# relayChain5.net
KiCad netlist of a schematic drawn in EAGLE
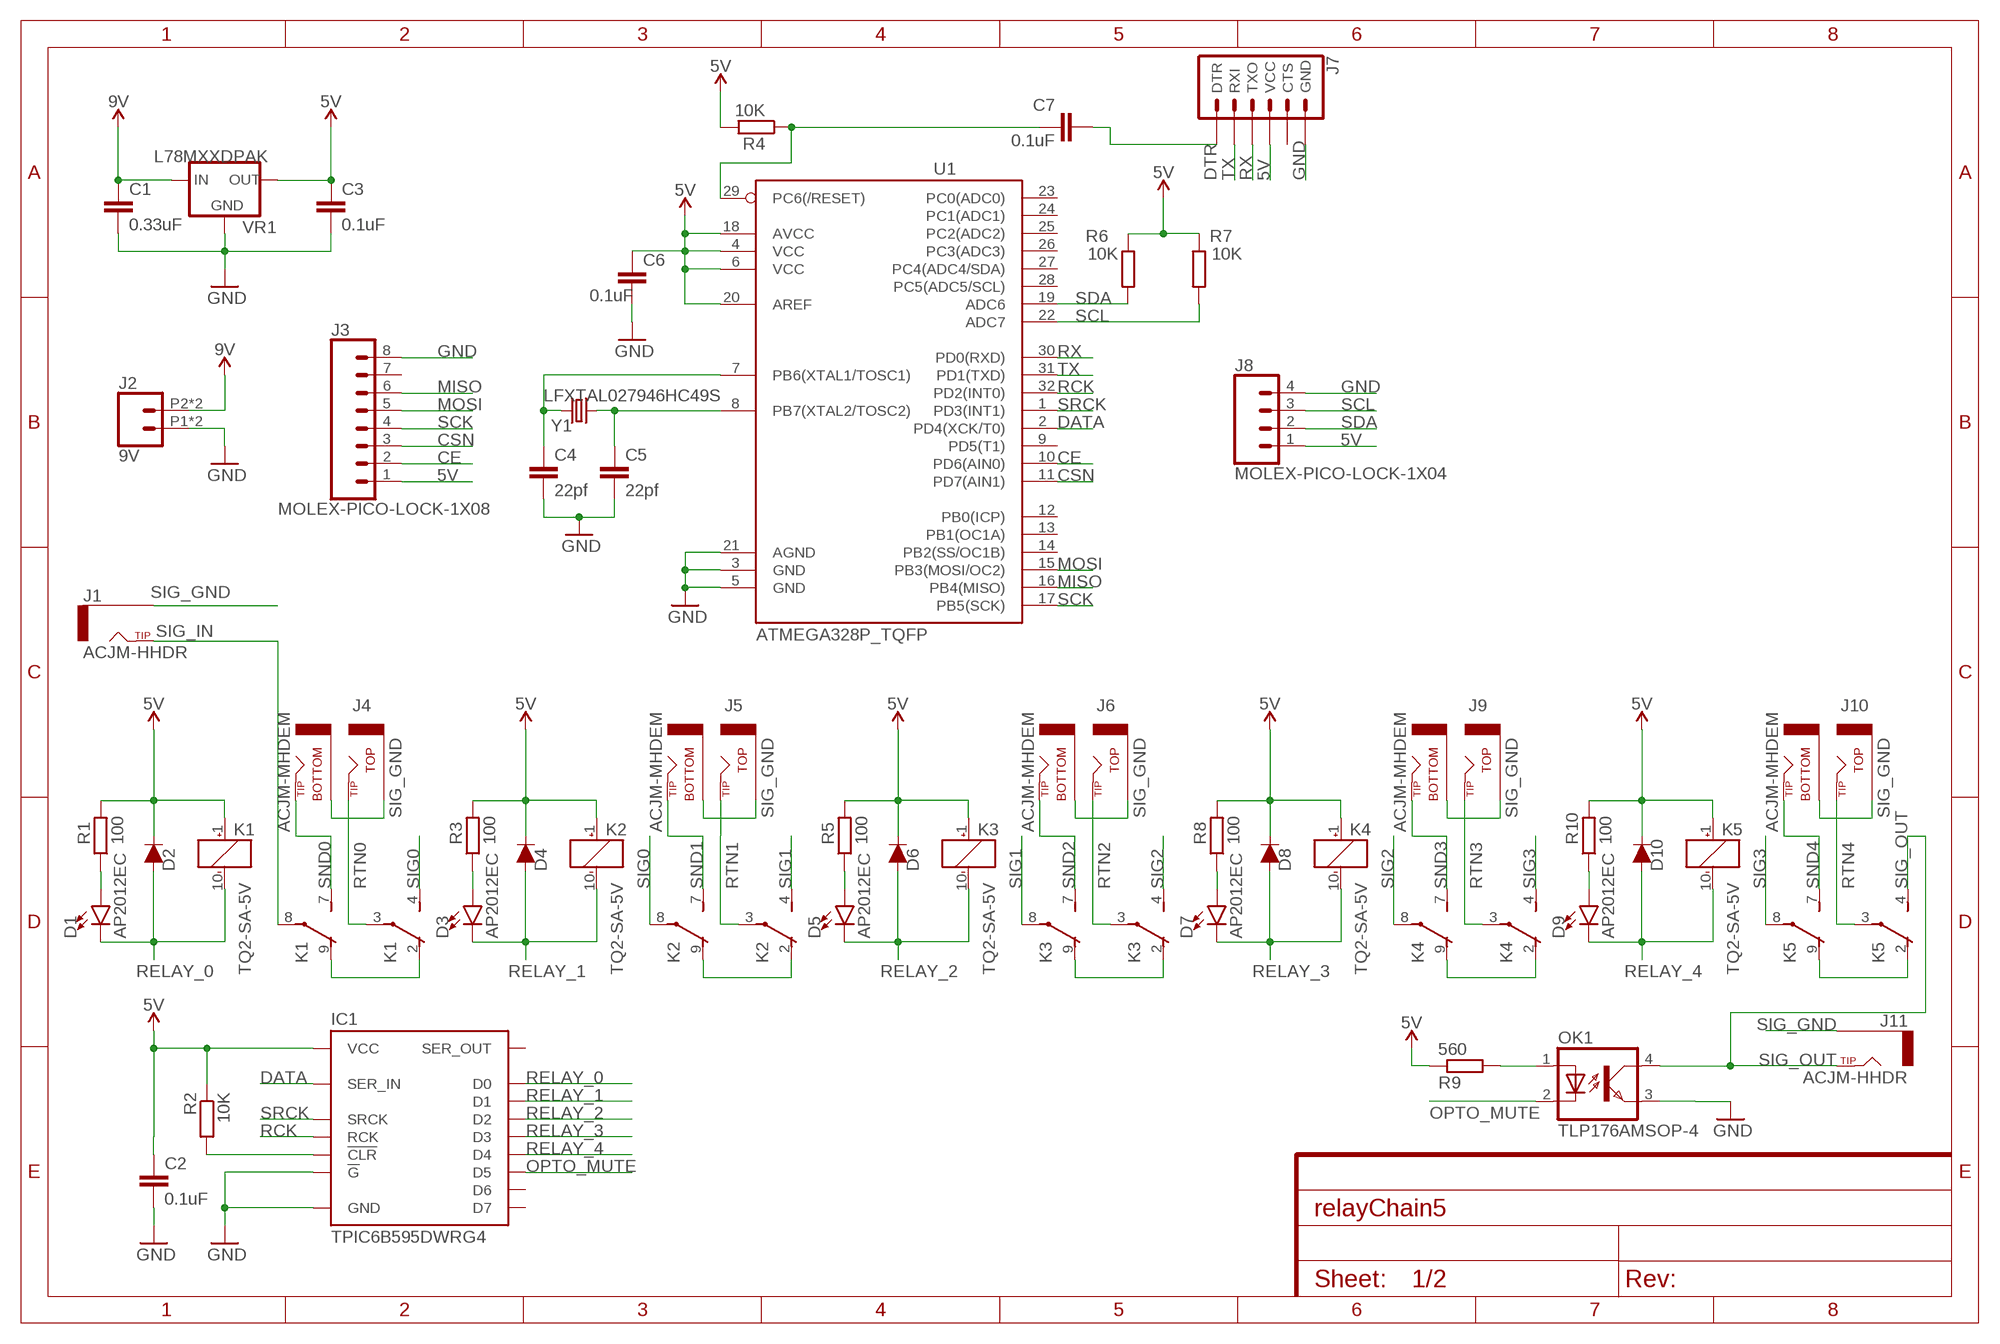
[diagram p0: schematic, sheet 1]
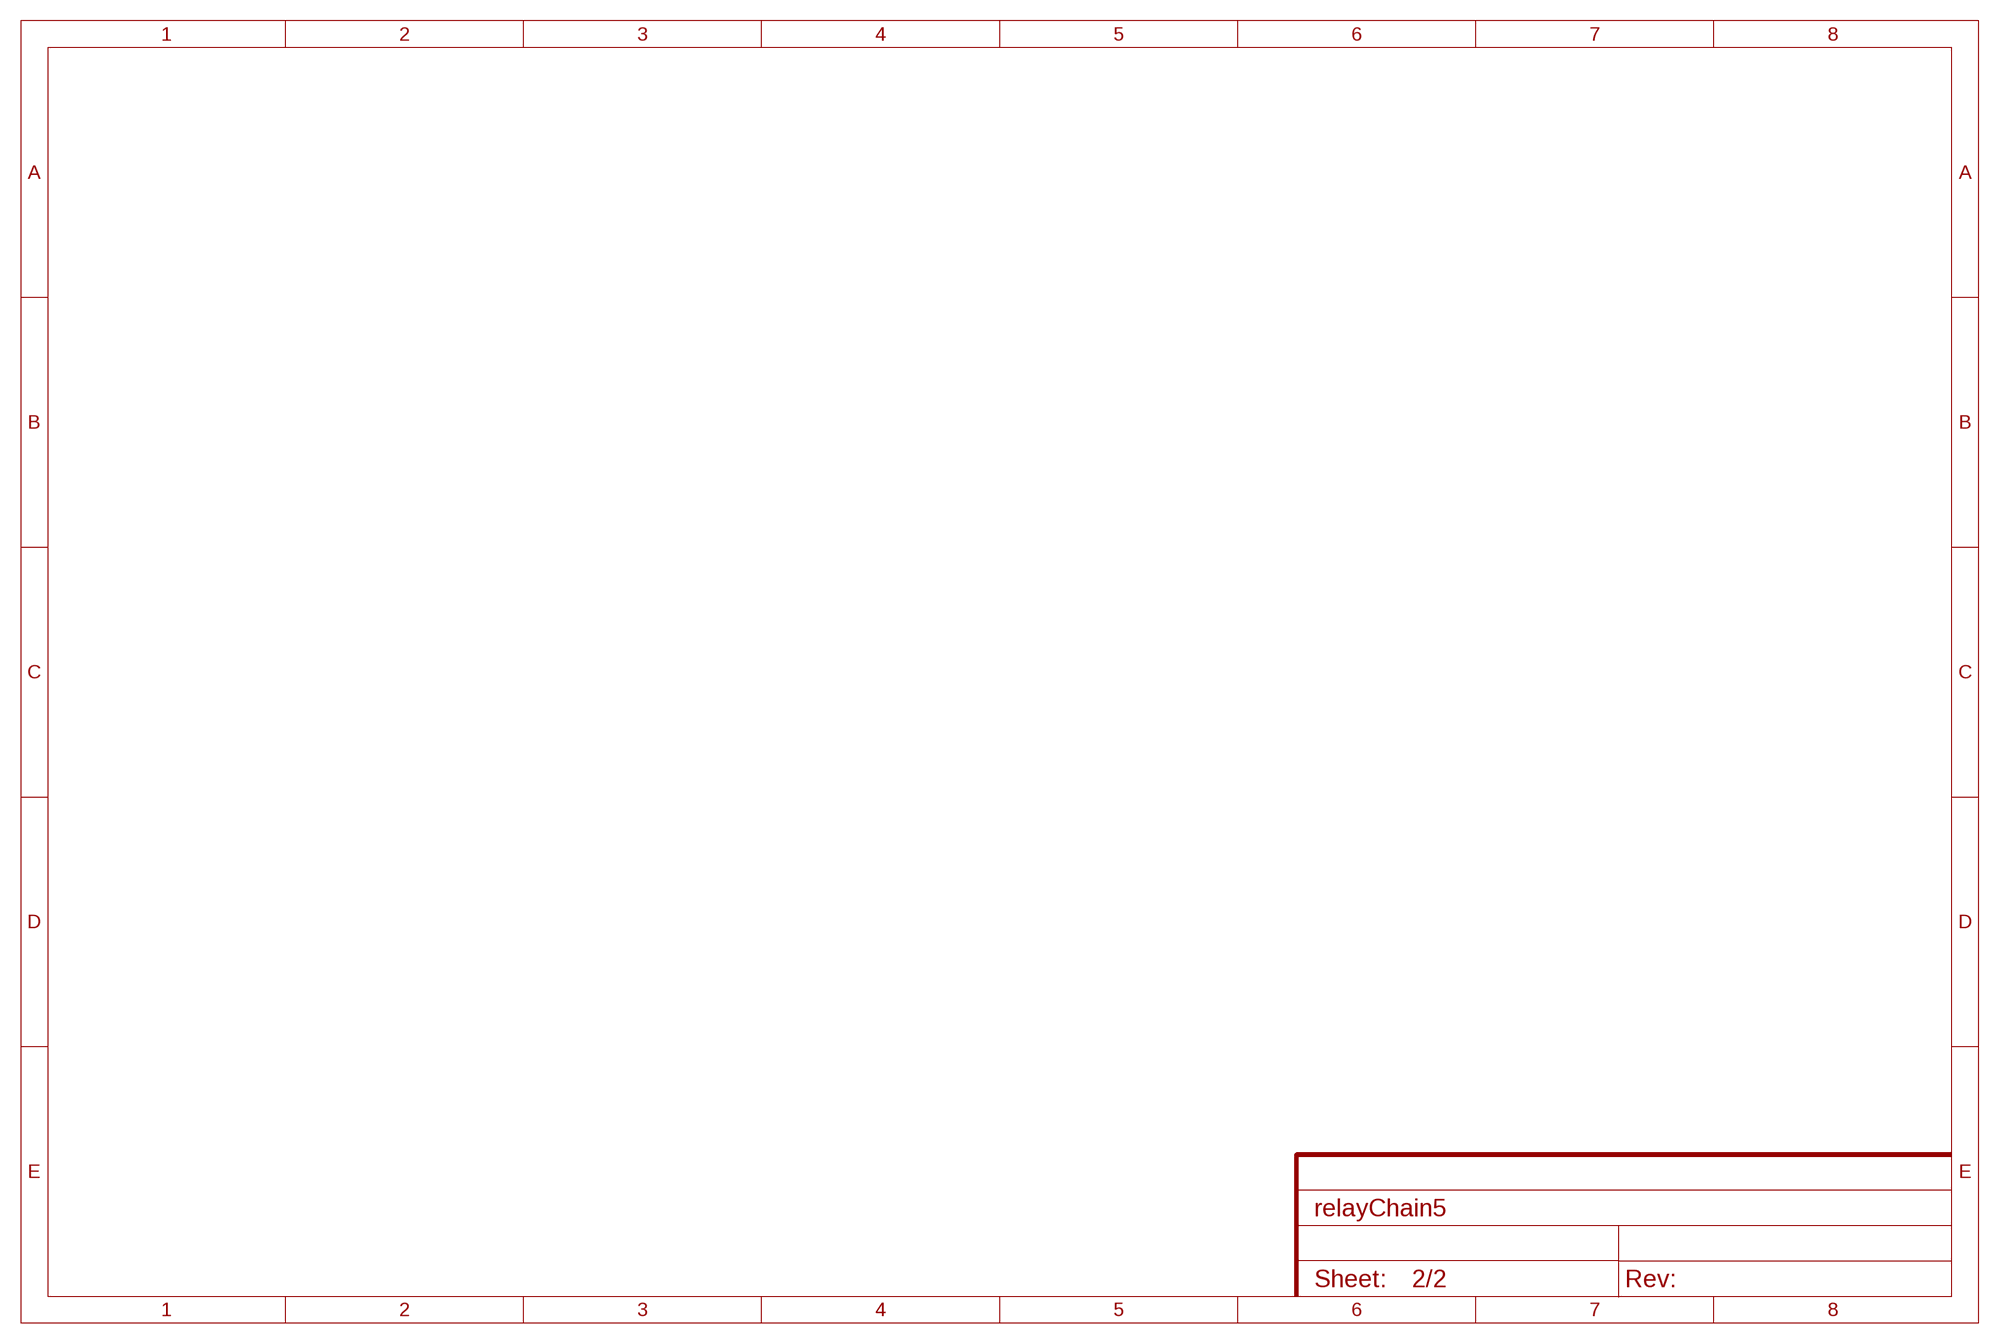
[diagram p1: schematic, sheet 2]

(export (version "E")
  (design (tool "Eeschema 10.0.6"))
  (components
    (comp (ref "C1")
      (value "0.33uF")
      (footprint "eagle-import:C0805")
      (libsource (lib "eagle-import") (part "C-EUC0805"))
    )
    (comp (ref "C2")
      (value "0.1uF")
      (footprint "eagle-import:C0805")
      (libsource (lib "eagle-import") (part "C-EUC0805"))
    )
    (comp (ref "C3")
      (value "0.1uF")
      (footprint "eagle-import:C0805")
      (libsource (lib "eagle-import") (part "C-EUC0805"))
    )
    (comp (ref "C4")
      (value "22pf")
      (footprint "eagle-import:C0805")
      (libsource (lib "eagle-import") (part "C-EUC0805"))
    )
    (comp (ref "C5")
      (value "22pf")
      (footprint "eagle-import:C0805")
      (libsource (lib "eagle-import") (part "C-EUC0805"))
    )
    (comp (ref "C6")
      (value "0.1uF")
      (footprint "eagle-import:C0805")
      (libsource (lib "eagle-import") (part "C-EUC0805"))
    )
    (comp (ref "C7")
      (value "0.1uF")
      (footprint "eagle-import:C0805")
      (libsource (lib "eagle-import") (part "C-EUC0805"))
    )
    (comp (ref "D1")
      (value "AP2012EC")
      (footprint "eagle-import:0805-LED-AP2012EC")
      (libsource (lib "eagle-import") (part "AP2012EC"))
    )
    (comp (ref "D2")
      (value "1n4148")
      (footprint "eagle-import:SOD-123_MINI-SMA")
      (libsource (lib "eagle-import") (part "621-1N4148?"))
    )
    (comp (ref "D3")
      (value "AP2012EC")
      (footprint "eagle-import:0805-LED-AP2012EC")
      (libsource (lib "eagle-import") (part "AP2012EC"))
    )
    (comp (ref "D4")
      (value "1n4148")
      (footprint "eagle-import:SOD-123_MINI-SMA")
      (libsource (lib "eagle-import") (part "621-1N4148?"))
    )
    (comp (ref "D5")
      (value "AP2012EC")
      (footprint "eagle-import:0805-LED-AP2012EC")
      (libsource (lib "eagle-import") (part "AP2012EC"))
    )
    (comp (ref "D6")
      (value "1n4148")
      (footprint "eagle-import:SOD-123_MINI-SMA")
      (libsource (lib "eagle-import") (part "621-1N4148?"))
    )
    (comp (ref "D7")
      (value "AP2012EC")
      (footprint "eagle-import:0805-LED-AP2012EC")
      (libsource (lib "eagle-import") (part "AP2012EC"))
    )
    (comp (ref "D8")
      (value "1n4148")
      (footprint "eagle-import:SOD-123_MINI-SMA")
      (libsource (lib "eagle-import") (part "621-1N4148?"))
    )
    (comp (ref "D9")
      (value "AP2012EC")
      (footprint "eagle-import:0805-LED-AP2012EC")
      (libsource (lib "eagle-import") (part "AP2012EC"))
    )
    (comp (ref "D10")
      (value "1n4148")
      (footprint "eagle-import:SOD-123_MINI-SMA")
      (libsource (lib "eagle-import") (part "621-1N4148?"))
    )
    (comp (ref "IC1")
      (value "TPIC6B595DWRG4")
      (footprint "eagle-import:SOIC127P1032X265-20")
      (libsource (lib "eagle-import") (part "TPIC6B595DWRG4"))
    )
    (comp (ref "J1")
      (value "ACJM-HHDR")
      (footprint "eagle-import:ACJM-HHDR")
      (libsource (lib "eagle-import") (part "ACJM-HHDR"))
    )
    (comp (ref "J2")
      (value "9V")
      (footprint "eagle-import:1X02_POKEHOME")
      (libsource (lib "eagle-import") (part "CONN_02SMALL_POKEHOME"))
    )
    (comp (ref "J3")
      (value "MOLEX-PICO-LOCK-1X08")
      (footprint "eagle-import:MOLEX-PICO-LOCK-1X08")
      (libsource (lib "eagle-import") (part "MOLEX-PICO-LOCK-1X08"))
    )
    (comp (ref "J4")
      (value "ACJM-MHDEM")
      (footprint "eagle-import:ACJM-MHDEM")
      (libsource (lib "eagle-import") (part "ACJM-MHDEM"))
    )
    (comp (ref "J5")
      (value "ACJM-MHDEM")
      (footprint "eagle-import:ACJM-MHDEM")
      (libsource (lib "eagle-import") (part "ACJM-MHDEM"))
    )
    (comp (ref "J6")
      (value "ACJM-MHDEM")
      (footprint "eagle-import:ACJM-MHDEM")
      (libsource (lib "eagle-import") (part "ACJM-MHDEM"))
    )
    (comp (ref "J7")
      (value "6_PIN_SERIAL_TARGETPTH-KIT")
      (footprint "eagle-import:1X06-KIT")
      (libsource (lib "eagle-import") (part "6_PIN_SERIAL_TARGETPTH-KIT"))
    )
    (comp (ref "J8")
      (value "MOLEX-PICO-LOCK-1X04")
      (footprint "eagle-import:MOLEX-PICO-LOCK-1X04")
      (libsource (lib "eagle-import") (part "MOLEX-PICO-LOCK-1X04"))
    )
    (comp (ref "J9")
      (value "ACJM-MHDEM")
      (footprint "eagle-import:ACJM-MHDEM")
      (libsource (lib "eagle-import") (part "ACJM-MHDEM"))
    )
    (comp (ref "J10")
      (value "ACJM-MHDEM")
      (footprint "eagle-import:ACJM-MHDEM")
      (libsource (lib "eagle-import") (part "ACJM-MHDEM"))
    )
    (comp (ref "J11")
      (value "ACJM-HHDR")
      (footprint "eagle-import:ACJM-HHDR")
      (libsource (lib "eagle-import") (part "ACJM-HHDR"))
    )
    (comp (ref "K1")
      (value "TQ2-SA-5V")
      (footprint "eagle-import:TQ-SA")
      (fields (field (name "MF") "AROMAT/ MATSUSHITA") (field (name "MPN") "TQ2SA-5V"))
      (libsource (lib "eagle-import") (part "TQ2?-SA-5V"))
    )
    (comp (ref "K2")
      (value "TQ2-SA-5V")
      (footprint "eagle-import:TQ-SA")
      (fields (field (name "MF") "AROMAT/ MATSUSHITA") (field (name "MPN") "TQ2SA-5V"))
      (libsource (lib "eagle-import") (part "TQ2?-SA-5V"))
    )
    (comp (ref "K3")
      (value "TQ2-SA-5V")
      (footprint "eagle-import:TQ-SA")
      (fields (field (name "MF") "AROMAT/ MATSUSHITA") (field (name "MPN") "TQ2SA-5V"))
      (libsource (lib "eagle-import") (part "TQ2?-SA-5V"))
    )
    (comp (ref "K4")
      (value "TQ2-SA-5V")
      (footprint "eagle-import:TQ-SA")
      (fields (field (name "MF") "AROMAT/ MATSUSHITA") (field (name "MPN") "TQ2SA-5V"))
      (libsource (lib "eagle-import") (part "TQ2?-SA-5V"))
    )
    (comp (ref "K5")
      (value "TQ2-SA-5V")
      (footprint "eagle-import:TQ-SA")
      (fields (field (name "MF") "AROMAT/ MATSUSHITA") (field (name "MPN") "TQ2SA-5V"))
      (libsource (lib "eagle-import") (part "TQ2?-SA-5V"))
    )
    (comp (ref "OK1")
      (value "TLP176AMSOP-4")
      (footprint "eagle-import:SOP254P715X220-4")
      (libsource (lib "eagle-import") (part "TLP176AMSOP-4"))
    )
    (comp (ref "R1")
      (value "100")
      (footprint "eagle-import:M2012")
      (libsource (lib "eagle-import") (part "R-EU_M2012"))
    )
    (comp (ref "R2")
      (value "10K")
      (footprint "eagle-import:R0805")
      (libsource (lib "eagle-import") (part "R-EU_R0805"))
    )
    (comp (ref "R3")
      (value "100")
      (footprint "eagle-import:M2012")
      (libsource (lib "eagle-import") (part "R-EU_M2012"))
    )
    (comp (ref "R4")
      (value "10K")
      (footprint "eagle-import:M2012")
      (libsource (lib "eagle-import") (part "R-EU_M2012"))
    )
    (comp (ref "R5")
      (value "100")
      (footprint "eagle-import:M2012")
      (libsource (lib "eagle-import") (part "R-EU_M2012"))
    )
    (comp (ref "R6")
      (value "10K")
      (footprint "eagle-import:M2012")
      (libsource (lib "eagle-import") (part "R-EU_M2012"))
    )
    (comp (ref "R7")
      (value "10K")
      (footprint "eagle-import:M2012")
      (libsource (lib "eagle-import") (part "R-EU_M2012"))
    )
    (comp (ref "R8")
      (value "100")
      (footprint "eagle-import:M2012")
      (libsource (lib "eagle-import") (part "R-EU_M2012"))
    )
    (comp (ref "R9")
      (value "560")
      (footprint "eagle-import:R0805")
      (libsource (lib "eagle-import") (part "R-EU_R0805"))
    )
    (comp (ref "R10")
      (value "100")
      (footprint "eagle-import:M2012")
      (libsource (lib "eagle-import") (part "R-EU_M2012"))
    )
    (comp (ref "U1")
      (value "ATMEGA328P_TQFP")
      (footprint "eagle-import:TQFP32-08")
      (libsource (lib "eagle-import") (part "ATMEGA328P_TQFP"))
    )
    (comp (ref "VR1")
      (value "L78MXXDPAK")
      (footprint "eagle-import:TO457P972X240-3")
      (libsource (lib "eagle-import") (part "L78MXX?DPAK"))
    )
    (comp (ref "Y1")
      (value "LFXTAL027946HC49S")
      (footprint "eagle-import:XTAL1150X490X450")
      (libsource (lib "eagle-import") (part "LFXTAL027946HC49S"))
    )
  )
  (nets
    (net (code "1") (name "5V") (class "Default")
      (node (ref "C2") (pin "1") (pinfunction "1_1") (pintype "passive"))
      (node (ref "C3") (pin "1") (pinfunction "1_1") (pintype "passive"))
      (node (ref "C6") (pin "1") (pinfunction "1_1") (pintype "passive"))
      (node (ref "D10") (pin "C") (pinfunction "C_C") (pintype "passive"))
      (node (ref "D2") (pin "C") (pinfunction "C_C") (pintype "passive"))
      (node (ref "D4") (pin "C") (pinfunction "C_C") (pintype "passive"))
      (node (ref "D6") (pin "C") (pinfunction "C_C") (pintype "passive"))
      (node (ref "D8") (pin "C") (pinfunction "C_C") (pintype "passive"))
      (node (ref "IC1") (pin "2") (pinfunction "VCC_2") (pintype "power_in"))
      (node (ref "J3") (pin "1") (pinfunction "1_1") (pintype "passive"))
      (node (ref "J7") (pin "4") (pinfunction "VCC_4") (pintype "passive"))
      (node (ref "J8") (pin "1") (pinfunction "1_1") (pintype "passive"))
      (node (ref "K1") (pin "1") (pinfunction "+_1") (pintype "passive"))
      (node (ref "K2") (pin "1") (pinfunction "+_1") (pintype "passive"))
      (node (ref "K3") (pin "1") (pinfunction "+_1") (pintype "passive"))
      (node (ref "K4") (pin "1") (pinfunction "+_1") (pintype "passive"))
      (node (ref "K5") (pin "1") (pinfunction "+_1") (pintype "passive"))
      (node (ref "R1") (pin "2") (pinfunction "2_2") (pintype "passive"))
      (node (ref "R10") (pin "2") (pinfunction "2_2") (pintype "passive"))
      (node (ref "R2") (pin "1") (pinfunction "1_1") (pintype "passive"))
      (node (ref "R3") (pin "2") (pinfunction "2_2") (pintype "passive"))
      (node (ref "R4") (pin "2") (pinfunction "2_2") (pintype "passive"))
      (node (ref "R5") (pin "2") (pinfunction "2_2") (pintype "passive"))
      (node (ref "R6") (pin "1") (pinfunction "1_1") (pintype "passive"))
      (node (ref "R7") (pin "1") (pinfunction "1_1") (pintype "passive"))
      (node (ref "R8") (pin "2") (pinfunction "2_2") (pintype "passive"))
      (node (ref "R9") (pin "1") (pinfunction "1_1") (pintype "passive"))
      (node (ref "U1") (pin "18") (pinfunction "AVCC_18") (pintype "bidirectional"))
      (node (ref "U1") (pin "20") (pinfunction "AREF_20") (pintype "bidirectional"))
      (node (ref "U1") (pin "4") (pinfunction "VCC_4") (pintype "bidirectional"))
      (node (ref "U1") (pin "6") (pinfunction "VCC_6") (pintype "bidirectional"))
      (node (ref "VR1") (pin "2") (pinfunction "OUT_2") (pintype "passive"))
    )
    (net (code "2") (name "9V") (class "Default")
      (node (ref "C1") (pin "1") (pinfunction "1_1") (pintype "passive"))
      (node (ref "J2") (pin "P2") (pinfunction "2_P2") (pintype "passive"))
      (node (ref "J2") (pin "P4") (pinfunction "2_P4") (pintype "passive"))
      (node (ref "VR1") (pin "1") (pinfunction "IN_1") (pintype "input"))
    )
    (net (code "3") (name "CE") (class "Default")
      (node (ref "J3") (pin "2") (pinfunction "2_2") (pintype "passive"))
      (node (ref "U1") (pin "10") (pinfunction "PD6(AIN0)_10") (pintype "bidirectional"))
    )
    (net (code "4") (name "CSN") (class "Default")
      (node (ref "J3") (pin "3") (pinfunction "3_3") (pintype "passive"))
      (node (ref "U1") (pin "11") (pinfunction "PD7(AIN1)_11") (pintype "bidirectional"))
    )
    (net (code "5") (name "DATA") (class "Default")
      (node (ref "IC1") (pin "3") (pinfunction "SER_IN_3") (pintype "input"))
      (node (ref "U1") (pin "2") (pinfunction "PD4(XCK/T0)_2") (pintype "bidirectional"))
    )
    (net (code "6") (name "DTR") (class "Default")
      (node (ref "C7") (pin "2") (pinfunction "2_2") (pintype "passive"))
      (node (ref "J7") (pin "1") (pinfunction "DTR_1") (pintype "passive"))
    )
    (net (code "7") (name "GND") (class "Default")
      (node (ref "C1") (pin "2") (pinfunction "2_2") (pintype "passive"))
      (node (ref "C2") (pin "2") (pinfunction "2_2") (pintype "passive"))
      (node (ref "C3") (pin "2") (pinfunction "2_2") (pintype "passive"))
      (node (ref "C4") (pin "2") (pinfunction "2_2") (pintype "passive"))
      (node (ref "C5") (pin "2") (pinfunction "2_2") (pintype "passive"))
      (node (ref "C6") (pin "2") (pinfunction "2_2") (pintype "passive"))
      (node (ref "IC1") (pin "10") (pinfunction "GND_10") (pintype "power_in"))
      (node (ref "IC1") (pin "11") (pinfunction "GND_11") (pintype "power_in"))
      (node (ref "IC1") (pin "19") (pinfunction "GND_19") (pintype "power_in"))
      (node (ref "IC1") (pin "9") (pinfunction "~{G}_9") (pintype "input"))
      (node (ref "J2") (pin "P1") (pinfunction "1_P1") (pintype "passive"))
      (node (ref "J2") (pin "P3") (pinfunction "1_P3") (pintype "passive"))
      (node (ref "J3") (pin "8") (pinfunction "8_8") (pintype "passive"))
      (node (ref "J7") (pin "6") (pinfunction "GND_6") (pintype "passive"))
      (node (ref "J8") (pin "4") (pinfunction "4_4") (pintype "passive"))
      (node (ref "OK1") (pin "3") (pinfunction "EMIT_3") (pintype "passive"))
      (node (ref "U1") (pin "21") (pinfunction "AGND_21") (pintype "bidirectional"))
      (node (ref "U1") (pin "3") (pinfunction "GND_3") (pintype "bidirectional"))
      (node (ref "U1") (pin "5") (pinfunction "GND_5") (pintype "bidirectional"))
      (node (ref "VR1") (pin "3") (pinfunction "GND_3") (pintype "input"))
    )
    (net (code "8") (name "MISO") (class "Default")
      (node (ref "J3") (pin "6") (pinfunction "6_6") (pintype "passive"))
      (node (ref "U1") (pin "16") (pinfunction "PB4(MISO)_16") (pintype "bidirectional"))
    )
    (net (code "9") (name "MOSI") (class "Default")
      (node (ref "J3") (pin "5") (pinfunction "5_5") (pintype "passive"))
      (node (ref "U1") (pin "15") (pinfunction "PB3(MOSI/OC2)_15") (pintype "bidirectional"))
    )
    (net (code "10") (name "Net-(D1-PadA)") (class "Default")
      (node (ref "D1") (pin "A") (pinfunction "A_A") (pintype "passive"))
      (node (ref "R1") (pin "1") (pinfunction "1_1") (pintype "passive"))
    )
    (net (code "11") (name "Net-(D3-PadA)") (class "Default")
      (node (ref "D3") (pin "A") (pinfunction "A_A") (pintype "passive"))
      (node (ref "R3") (pin "1") (pinfunction "1_1") (pintype "passive"))
    )
    (net (code "12") (name "Net-(D5-PadA)") (class "Default")
      (node (ref "D5") (pin "A") (pinfunction "A_A") (pintype "passive"))
      (node (ref "R5") (pin "1") (pinfunction "1_1") (pintype "passive"))
    )
    (net (code "13") (name "Net-(D7-PadA)") (class "Default")
      (node (ref "D7") (pin "A") (pinfunction "A_A") (pintype "passive"))
      (node (ref "R8") (pin "1") (pinfunction "1_1") (pintype "passive"))
    )
    (net (code "14") (name "Net-(D9-PadA)") (class "Default")
      (node (ref "D9") (pin "A") (pinfunction "A_A") (pintype "passive"))
      (node (ref "R10") (pin "1") (pinfunction "1_1") (pintype "passive"))
    )
    (net (code "15") (name "Net-(IC1-~{CLR})") (class "Default")
      (node (ref "IC1") (pin "8") (pinfunction "~{CLR}_8") (pintype "input"))
      (node (ref "R2") (pin "2") (pinfunction "2_2") (pintype "passive"))
    )
    (net (code "16") (name "Net-(K1A-O)") (class "Default")
      (node (ref "K1") (pin "2") (pinfunction "O_2") (pintype "passive"))
      (node (ref "K1") (pin "9") (pinfunction "O_9") (pintype "passive"))
    )
    (net (code "17") (name "Net-(K2A-O)") (class "Default")
      (node (ref "K2") (pin "2") (pinfunction "O_2") (pintype "passive"))
      (node (ref "K2") (pin "9") (pinfunction "O_9") (pintype "passive"))
    )
    (net (code "18") (name "Net-(K3A-O)") (class "Default")
      (node (ref "K3") (pin "2") (pinfunction "O_2") (pintype "passive"))
      (node (ref "K3") (pin "9") (pinfunction "O_9") (pintype "passive"))
    )
    (net (code "19") (name "Net-(K4A-O)") (class "Default")
      (node (ref "K4") (pin "2") (pinfunction "O_2") (pintype "passive"))
      (node (ref "K4") (pin "9") (pinfunction "O_9") (pintype "passive"))
    )
    (net (code "20") (name "Net-(K5A-O)") (class "Default")
      (node (ref "K5") (pin "2") (pinfunction "O_2") (pintype "passive"))
      (node (ref "K5") (pin "9") (pinfunction "O_9") (pintype "passive"))
    )
    (net (code "21") (name "Net-(OK1-A)") (class "Default")
      (node (ref "OK1") (pin "1") (pinfunction "A_1") (pintype "passive"))
      (node (ref "R9") (pin "2") (pinfunction "2_2") (pintype "passive"))
    )
    (net (code "22") (name "Net-(U1-PB6(XTAL1{slash}TOSC1))") (class "Default")
      (node (ref "C4") (pin "1") (pinfunction "1_1") (pintype "passive"))
      (node (ref "U1") (pin "7") (pinfunction "PB6(XTAL1/TOSC1)_7") (pintype "bidirectional"))
      (node (ref "Y1") (pin "1") (pinfunction "1_1") (pintype "passive"))
    )
    (net (code "23") (name "Net-(U1-PB7(XTAL2{slash}TOSC2))") (class "Default")
      (node (ref "C5") (pin "1") (pinfunction "1_1") (pintype "passive"))
      (node (ref "U1") (pin "8") (pinfunction "PB7(XTAL2/TOSC2)_8") (pintype "bidirectional"))
      (node (ref "Y1") (pin "2") (pinfunction "2_2") (pintype "passive"))
    )
    (net (code "24") (name "Net-(U1-PC6({slash}RESET))") (class "Default")
      (node (ref "C7") (pin "1") (pinfunction "1_1") (pintype "passive"))
      (node (ref "R4") (pin "1") (pinfunction "1_1") (pintype "passive"))
      (node (ref "U1") (pin "29") (pinfunction "PC6(/RESET)_29") (pintype "bidirectional"))
    )
    (net (code "25") (name "OPTO_MUTE") (class "Default")
      (node (ref "IC1") (pin "15") (pinfunction "D5_15") (pintype "output"))
      (node (ref "OK1") (pin "2") (pinfunction "C_2") (pintype "passive"))
    )
    (net (code "26") (name "RCK") (class "Default")
      (node (ref "IC1") (pin "12") (pinfunction "RCK_12") (pintype "input"))
      (node (ref "U1") (pin "32") (pinfunction "PD2(INT0)_32") (pintype "bidirectional"))
    )
    (net (code "27") (name "RELAY_0") (class "Default")
      (node (ref "D1") (pin "C") (pinfunction "C_C") (pintype "passive"))
      (node (ref "D2") (pin "A") (pinfunction "A_A") (pintype "passive"))
      (node (ref "IC1") (pin "4") (pinfunction "D0_4") (pintype "output"))
      (node (ref "K1") (pin "10") (pinfunction "-_10") (pintype "passive"))
    )
    (net (code "28") (name "RELAY_1") (class "Default")
      (node (ref "D3") (pin "C") (pinfunction "C_C") (pintype "passive"))
      (node (ref "D4") (pin "A") (pinfunction "A_A") (pintype "passive"))
      (node (ref "IC1") (pin "5") (pinfunction "D1_5") (pintype "output"))
      (node (ref "K2") (pin "10") (pinfunction "-_10") (pintype "passive"))
    )
    (net (code "29") (name "RELAY_2") (class "Default")
      (node (ref "D5") (pin "C") (pinfunction "C_C") (pintype "passive"))
      (node (ref "D6") (pin "A") (pinfunction "A_A") (pintype "passive"))
      (node (ref "IC1") (pin "6") (pinfunction "D2_6") (pintype "output"))
      (node (ref "K3") (pin "10") (pinfunction "-_10") (pintype "passive"))
    )
    (net (code "30") (name "RELAY_3") (class "Default")
      (node (ref "D7") (pin "C") (pinfunction "C_C") (pintype "passive"))
      (node (ref "D8") (pin "A") (pinfunction "A_A") (pintype "passive"))
      (node (ref "IC1") (pin "7") (pinfunction "D3_7") (pintype "output"))
      (node (ref "K4") (pin "10") (pinfunction "-_10") (pintype "passive"))
    )
    (net (code "31") (name "RELAY_4") (class "Default")
      (node (ref "D10") (pin "A") (pinfunction "A_A") (pintype "passive"))
      (node (ref "D9") (pin "C") (pinfunction "C_C") (pintype "passive"))
      (node (ref "IC1") (pin "14") (pinfunction "D4_14") (pintype "output"))
      (node (ref "K5") (pin "10") (pinfunction "-_10") (pintype "passive"))
    )
    (net (code "32") (name "RTN0") (class "Default")
      (node (ref "J4") (pin "12") (pinfunction "TIP_TOP_12") (pintype "bidirectional"))
      (node (ref "J4") (pin "9") (pinfunction "TIP_TOP_9") (pintype "bidirectional"))
      (node (ref "K1") (pin "3") (pinfunction "P_3") (pintype "passive"))
    )
    (net (code "33") (name "RTN1") (class "Default")
      (node (ref "J5") (pin "12") (pinfunction "TIP_TOP_12") (pintype "bidirectional"))
      (node (ref "J5") (pin "9") (pinfunction "TIP_TOP_9") (pintype "bidirectional"))
      (node (ref "K2") (pin "3") (pinfunction "P_3") (pintype "passive"))
    )
    (net (code "34") (name "RTN2") (class "Default")
      (node (ref "J6") (pin "12") (pinfunction "TIP_TOP_12") (pintype "bidirectional"))
      (node (ref "J6") (pin "9") (pinfunction "TIP_TOP_9") (pintype "bidirectional"))
      (node (ref "K3") (pin "3") (pinfunction "P_3") (pintype "passive"))
    )
    (net (code "35") (name "RTN3") (class "Default")
      (node (ref "J9") (pin "12") (pinfunction "TIP_TOP_12") (pintype "bidirectional"))
      (node (ref "J9") (pin "9") (pinfunction "TIP_TOP_9") (pintype "bidirectional"))
      (node (ref "K4") (pin "3") (pinfunction "P_3") (pintype "passive"))
    )
    (net (code "36") (name "RTN4") (class "Default")
      (node (ref "J10") (pin "12") (pinfunction "TIP_TOP_12") (pintype "bidirectional"))
      (node (ref "J10") (pin "9") (pinfunction "TIP_TOP_9") (pintype "bidirectional"))
      (node (ref "K5") (pin "3") (pinfunction "P_3") (pintype "passive"))
    )
    (net (code "37") (name "RX") (class "Default")
      (node (ref "J7") (pin "3") (pinfunction "TXO_3") (pintype "passive"))
      (node (ref "U1") (pin "30") (pinfunction "PD0(RXD)_30") (pintype "bidirectional"))
    )
    (net (code "38") (name "SCK") (class "Default")
      (node (ref "J3") (pin "4") (pinfunction "4_4") (pintype "passive"))
      (node (ref "U1") (pin "17") (pinfunction "PB5(SCK)_17") (pintype "bidirectional"))
    )
    (net (code "39") (name "SCL") (class "Default")
      (node (ref "J8") (pin "3") (pinfunction "3_3") (pintype "passive"))
      (node (ref "R7") (pin "2") (pinfunction "2_2") (pintype "passive"))
      (node (ref "U1") (pin "22") (pinfunction "ADC7_22") (pintype "bidirectional"))
    )
    (net (code "40") (name "SDA") (class "Default")
      (node (ref "J8") (pin "2") (pinfunction "2_2") (pintype "passive"))
      (node (ref "R6") (pin "2") (pinfunction "2_2") (pintype "passive"))
      (node (ref "U1") (pin "19") (pinfunction "ADC6_19") (pintype "bidirectional"))
    )
    (net (code "41") (name "SIG0") (class "Default")
      (node (ref "K1") (pin "4") (pinfunction "S_4") (pintype "passive"))
      (node (ref "K2") (pin "8") (pinfunction "P_8") (pintype "passive"))
    )
    (net (code "42") (name "SIG1") (class "Default")
      (node (ref "K2") (pin "4") (pinfunction "S_4") (pintype "passive"))
      (node (ref "K3") (pin "8") (pinfunction "P_8") (pintype "passive"))
    )
    (net (code "43") (name "SIG2") (class "Default")
      (node (ref "K3") (pin "4") (pinfunction "S_4") (pintype "passive"))
      (node (ref "K4") (pin "8") (pinfunction "P_8") (pintype "passive"))
    )
    (net (code "44") (name "SIG3") (class "Default")
      (node (ref "K4") (pin "4") (pinfunction "S_4") (pintype "passive"))
      (node (ref "K5") (pin "8") (pinfunction "P_8") (pintype "passive"))
    )
    (net (code "45") (name "SIG_GND") (class "Default")
      (node (ref "J1") (pin "SLEEVE_1") (pinfunction "SLEEVE_SLEEVE_1") (pintype "bidirectional"))
      (node (ref "J1") (pin "SLEEVE_2") (pinfunction "SLEEVE_SLEEVE_2") (pintype "bidirectional"))
      (node (ref "J10") (pin "1") (pinfunction "SLEEVE_BOTTOM_1") (pintype "bidirectional"))
      (node (ref "J10") (pin "10") (pinfunction "SLEEVE_TOP_10") (pintype "bidirectional"))
      (node (ref "J10") (pin "4") (pinfunction "SLEEVE_BOTTOM_4") (pintype "bidirectional"))
      (node (ref "J10") (pin "7") (pinfunction "SLEEVE_TOP_7") (pintype "bidirectional"))
      (node (ref "J11") (pin "SLEEVE_1") (pinfunction "SLEEVE_SLEEVE_1") (pintype "bidirectional"))
      (node (ref "J11") (pin "SLEEVE_2") (pinfunction "SLEEVE_SLEEVE_2") (pintype "bidirectional"))
      (node (ref "J4") (pin "1") (pinfunction "SLEEVE_BOTTOM_1") (pintype "bidirectional"))
      (node (ref "J4") (pin "10") (pinfunction "SLEEVE_TOP_10") (pintype "bidirectional"))
      (node (ref "J4") (pin "4") (pinfunction "SLEEVE_BOTTOM_4") (pintype "bidirectional"))
      (node (ref "J4") (pin "7") (pinfunction "SLEEVE_TOP_7") (pintype "bidirectional"))
      (node (ref "J5") (pin "1") (pinfunction "SLEEVE_BOTTOM_1") (pintype "bidirectional"))
      (node (ref "J5") (pin "10") (pinfunction "SLEEVE_TOP_10") (pintype "bidirectional"))
      (node (ref "J5") (pin "4") (pinfunction "SLEEVE_BOTTOM_4") (pintype "bidirectional"))
      (node (ref "J5") (pin "7") (pinfunction "SLEEVE_TOP_7") (pintype "bidirectional"))
      (node (ref "J6") (pin "1") (pinfunction "SLEEVE_BOTTOM_1") (pintype "bidirectional"))
      (node (ref "J6") (pin "10") (pinfunction "SLEEVE_TOP_10") (pintype "bidirectional"))
      (node (ref "J6") (pin "4") (pinfunction "SLEEVE_BOTTOM_4") (pintype "bidirectional"))
      (node (ref "J6") (pin "7") (pinfunction "SLEEVE_TOP_7") (pintype "bidirectional"))
      (node (ref "J9") (pin "1") (pinfunction "SLEEVE_BOTTOM_1") (pintype "bidirectional"))
      (node (ref "J9") (pin "10") (pinfunction "SLEEVE_TOP_10") (pintype "bidirectional"))
      (node (ref "J9") (pin "4") (pinfunction "SLEEVE_BOTTOM_4") (pintype "bidirectional"))
      (node (ref "J9") (pin "7") (pinfunction "SLEEVE_TOP_7") (pintype "bidirectional"))
    )
    (net (code "46") (name "SIG_IN") (class "Default")
      (node (ref "J1") (pin "TIP_1") (pinfunction "TIP_TIP_1") (pintype "bidirectional"))
      (node (ref "J1") (pin "TIP_2") (pinfunction "TIP_TIP_2") (pintype "bidirectional"))
      (node (ref "K1") (pin "8") (pinfunction "P_8") (pintype "passive"))
    )
    (net (code "47") (name "SIG_OUT") (class "Default")
      (node (ref "J11") (pin "TIP_1") (pinfunction "TIP_TIP_1") (pintype "bidirectional"))
      (node (ref "J11") (pin "TIP_2") (pinfunction "TIP_TIP_2") (pintype "bidirectional"))
      (node (ref "K5") (pin "4") (pinfunction "S_4") (pintype "passive"))
      (node (ref "OK1") (pin "4") (pinfunction "COL_4") (pintype "passive"))
    )
    (net (code "48") (name "SND0") (class "Default")
      (node (ref "J4") (pin "3") (pinfunction "TIP_BOTTOM_3") (pintype "bidirectional"))
      (node (ref "J4") (pin "6") (pinfunction "TIP_BOTTOM_6") (pintype "bidirectional"))
      (node (ref "K1") (pin "7") (pinfunction "S_7") (pintype "passive"))
    )
    (net (code "49") (name "SND1") (class "Default")
      (node (ref "J5") (pin "3") (pinfunction "TIP_BOTTOM_3") (pintype "bidirectional"))
      (node (ref "J5") (pin "6") (pinfunction "TIP_BOTTOM_6") (pintype "bidirectional"))
      (node (ref "K2") (pin "7") (pinfunction "S_7") (pintype "passive"))
    )
    (net (code "50") (name "SND2") (class "Default")
      (node (ref "J6") (pin "3") (pinfunction "TIP_BOTTOM_3") (pintype "bidirectional"))
      (node (ref "J6") (pin "6") (pinfunction "TIP_BOTTOM_6") (pintype "bidirectional"))
      (node (ref "K3") (pin "7") (pinfunction "S_7") (pintype "passive"))
    )
    (net (code "51") (name "SND3") (class "Default")
      (node (ref "J9") (pin "3") (pinfunction "TIP_BOTTOM_3") (pintype "bidirectional"))
      (node (ref "J9") (pin "6") (pinfunction "TIP_BOTTOM_6") (pintype "bidirectional"))
      (node (ref "K4") (pin "7") (pinfunction "S_7") (pintype "passive"))
    )
    (net (code "52") (name "SND4") (class "Default")
      (node (ref "J10") (pin "3") (pinfunction "TIP_BOTTOM_3") (pintype "bidirectional"))
      (node (ref "J10") (pin "6") (pinfunction "TIP_BOTTOM_6") (pintype "bidirectional"))
      (node (ref "K5") (pin "7") (pinfunction "S_7") (pintype "passive"))
    )
    (net (code "53") (name "SRCK") (class "Default")
      (node (ref "IC1") (pin "13") (pinfunction "SRCK_13") (pintype "input"))
      (node (ref "U1") (pin "1") (pinfunction "PD3(INT1)_1") (pintype "bidirectional"))
    )
    (net (code "54") (name "TX") (class "Default")
      (node (ref "J7") (pin "2") (pinfunction "RXI_2") (pintype "passive"))
      (node (ref "U1") (pin "31") (pinfunction "PD1(TXD)_31") (pintype "bidirectional"))
    )
    (net (code "55") (name "unconnected-(IC1-D6-Pad16)") (class "Default")
      (node (ref "IC1") (pin "16") (pinfunction "D6_16") (pintype "output"))
    )
    (net (code "56") (name "unconnected-(IC1-D7-Pad17)") (class "Default")
      (node (ref "IC1") (pin "17") (pinfunction "D7_17") (pintype "output"))
    )
    (net (code "57") (name "unconnected-(IC1-SER_OUT-Pad18)") (class "Default")
      (node (ref "IC1") (pin "18") (pinfunction "SER_OUT_18") (pintype "output"))
    )
    (net (code "58") (name "unconnected-(J3-Pad7)") (class "Default")
      (node (ref "J3") (pin "7") (pinfunction "7_7") (pintype "passive"))
    )
    (net (code "59") (name "unconnected-(J7-CTS-Pad5)") (class "Default")
      (node (ref "J7") (pin "5") (pinfunction "CTS_5") (pintype "passive"))
    )
    (net (code "60") (name "unconnected-(U1-PB0(ICP)-Pad12)") (class "Default")
      (node (ref "U1") (pin "12") (pinfunction "PB0(ICP)_12") (pintype "bidirectional"))
    )
    (net (code "61") (name "unconnected-(U1-PB1(OC1A)-Pad13)") (class "Default")
      (node (ref "U1") (pin "13") (pinfunction "PB1(OC1A)_13") (pintype "bidirectional"))
    )
    (net (code "62") (name "unconnected-(U1-PB2(SS{slash}OC1B)-Pad14)") (class "Default")
      (node (ref "U1") (pin "14") (pinfunction "PB2(SS/OC1B)_14") (pintype "bidirectional"))
    )
    (net (code "63") (name "unconnected-(U1-PC0(ADC0)-Pad23)") (class "Default")
      (node (ref "U1") (pin "23") (pinfunction "PC0(ADC0)_23") (pintype "bidirectional"))
    )
    (net (code "64") (name "unconnected-(U1-PC1(ADC1)-Pad24)") (class "Default")
      (node (ref "U1") (pin "24") (pinfunction "PC1(ADC1)_24") (pintype "bidirectional"))
    )
    (net (code "65") (name "unconnected-(U1-PC2(ADC2)-Pad25)") (class "Default")
      (node (ref "U1") (pin "25") (pinfunction "PC2(ADC2)_25") (pintype "bidirectional"))
    )
    (net (code "66") (name "unconnected-(U1-PC3(ADC3)-Pad26)") (class "Default")
      (node (ref "U1") (pin "26") (pinfunction "PC3(ADC3)_26") (pintype "bidirectional"))
    )
    (net (code "67") (name "unconnected-(U1-PC4(ADC4{slash}SDA)-Pad27)") (class "Default")
      (node (ref "U1") (pin "27") (pinfunction "PC4(ADC4/SDA)_27") (pintype "bidirectional"))
    )
    (net (code "68") (name "unconnected-(U1-PC5(ADC5{slash}SCL)-Pad28)") (class "Default")
      (node (ref "U1") (pin "28") (pinfunction "PC5(ADC5/SCL)_28") (pintype "bidirectional"))
    )
    (net (code "69") (name "unconnected-(U1-PD5(T1)-Pad9)") (class "Default")
      (node (ref "U1") (pin "9") (pinfunction "PD5(T1)_9") (pintype "bidirectional"))
    )
  )
)
